# multiplex.net
KiCad netlist of a schematic drawn in EAGLE
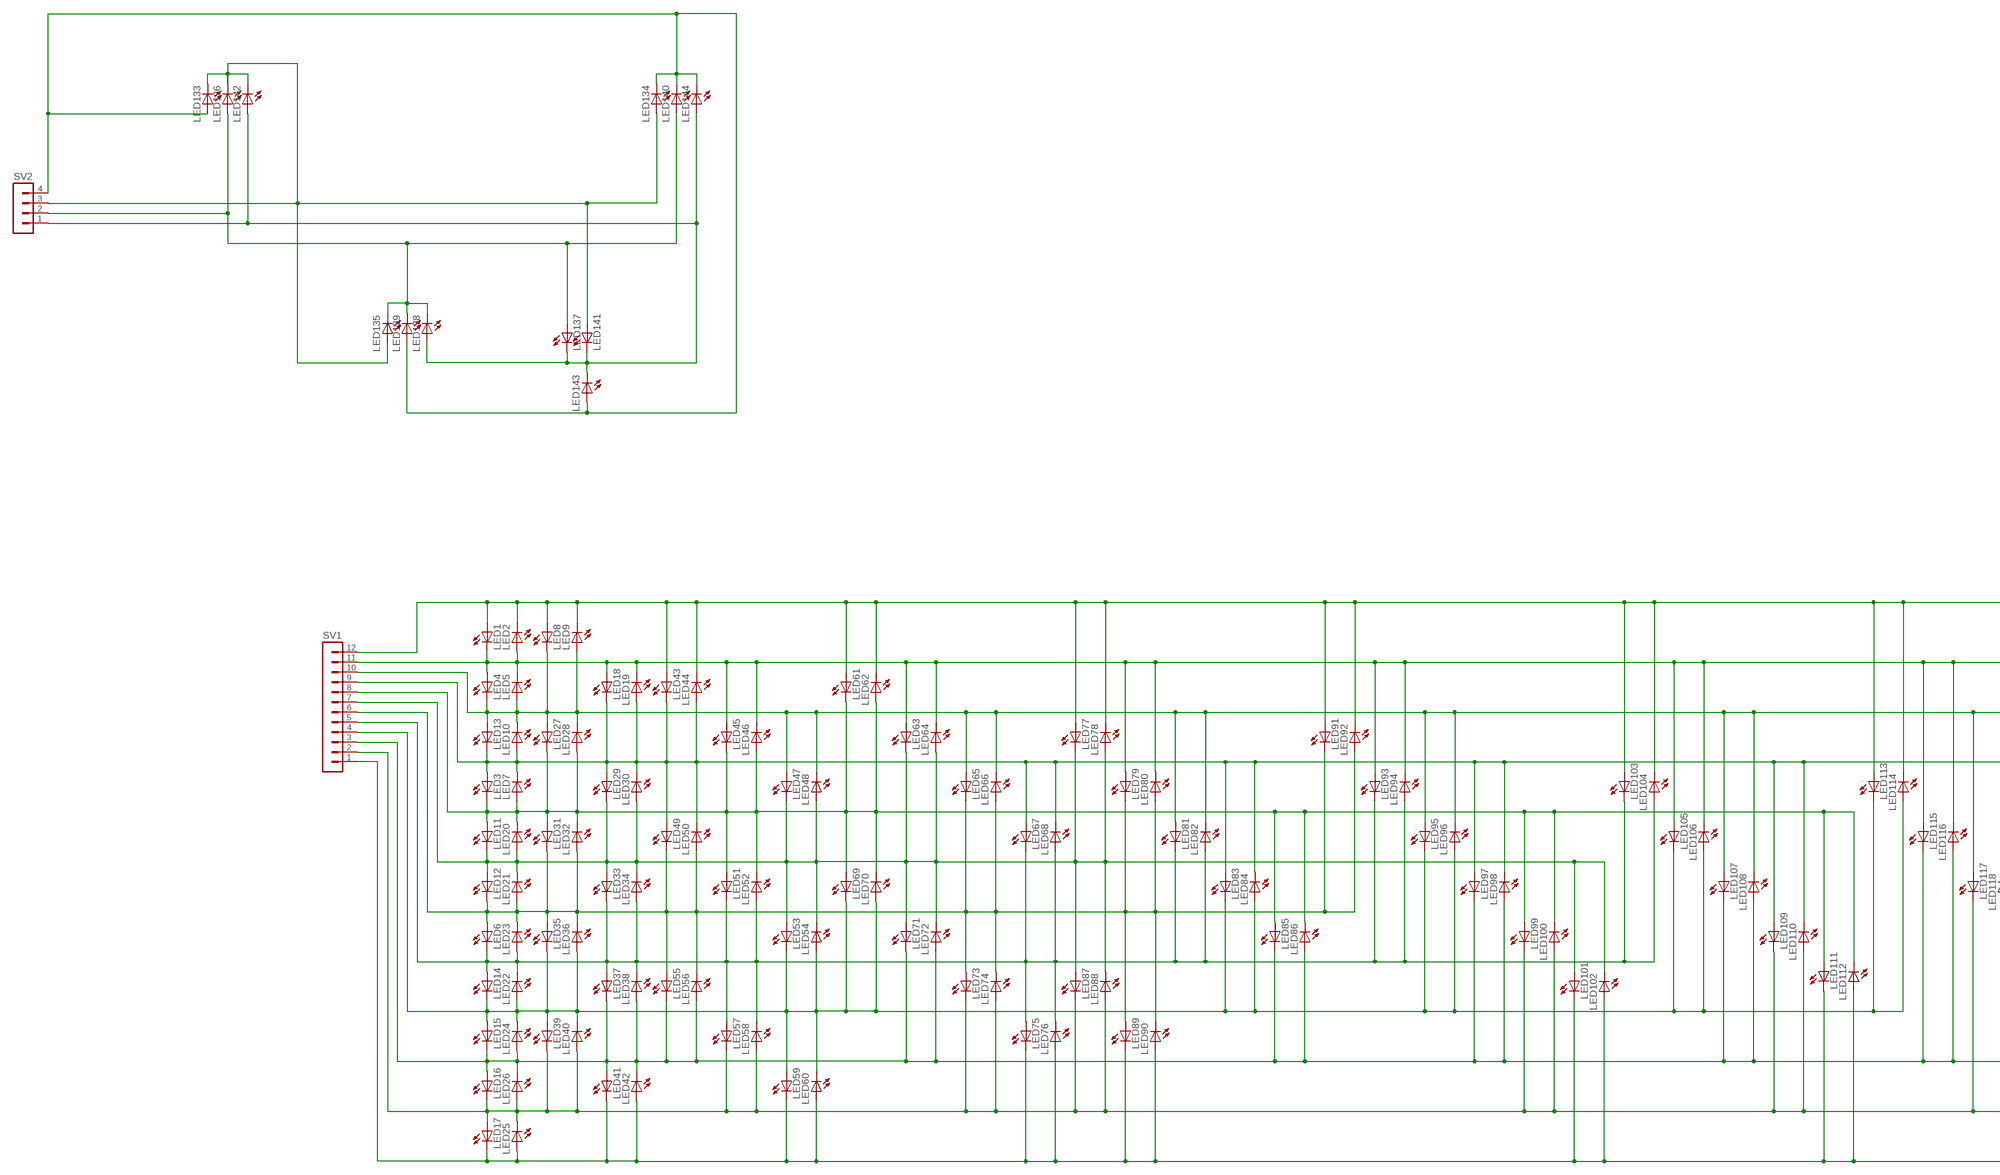
[diagram p0: schematic, sheet 1, part 1 of 2]
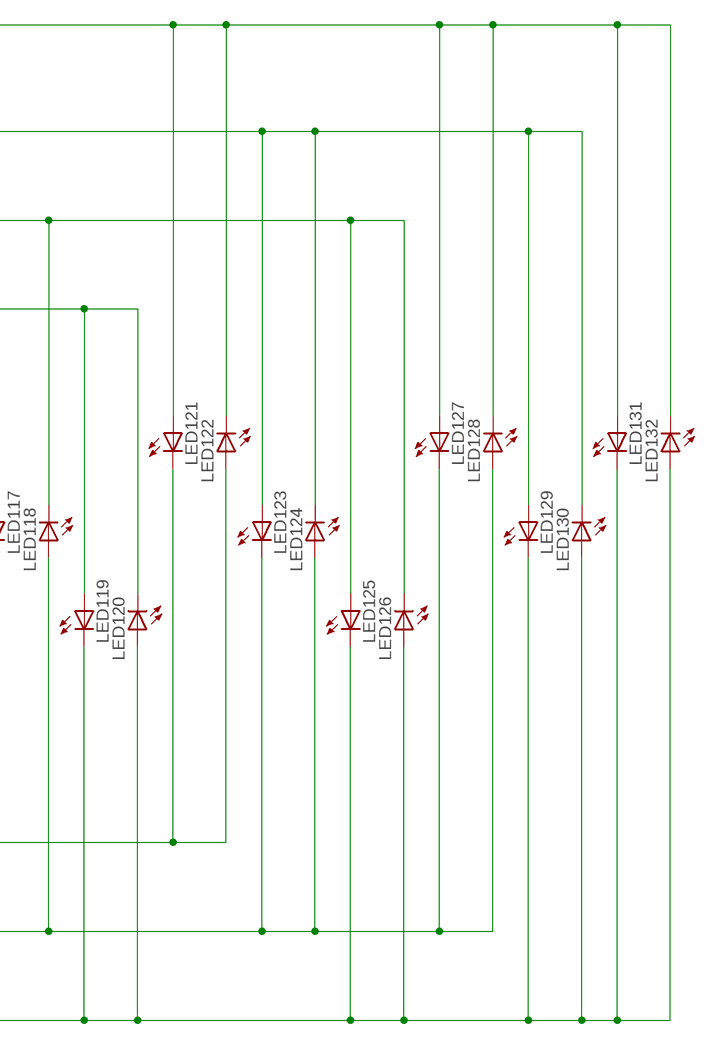
[diagram p1: schematic, sheet 1, part 2 of 2]

(export (version "E")
  (design (tool "Eeschema 10.0.6"))
  (components
    (comp (ref "LED1")
      (value "LED5MM")
      (footprint "eagle-import:LED5MM")
      (libsource (lib "eagle-import") (part "LED5MM"))
    )
    (comp (ref "LED2")
      (value "LED5MM")
      (footprint "eagle-import:LED5MM")
      (libsource (lib "eagle-import") (part "LED5MM"))
    )
    (comp (ref "LED3")
      (value "LED5MM")
      (footprint "eagle-import:LED5MM")
      (libsource (lib "eagle-import") (part "LED5MM"))
    )
    (comp (ref "LED4")
      (value "LED5MM")
      (footprint "eagle-import:LED5MM")
      (libsource (lib "eagle-import") (part "LED5MM"))
    )
    (comp (ref "LED5")
      (value "LED5MM")
      (footprint "eagle-import:LED5MM")
      (libsource (lib "eagle-import") (part "LED5MM"))
    )
    (comp (ref "LED6")
      (value "LED5MM")
      (footprint "eagle-import:LED5MM")
      (libsource (lib "eagle-import") (part "LED5MM"))
    )
    (comp (ref "LED7")
      (value "LED5MM")
      (footprint "eagle-import:LED5MM")
      (libsource (lib "eagle-import") (part "LED5MM"))
    )
    (comp (ref "LED8")
      (value "LED5MM")
      (footprint "eagle-import:LED5MM")
      (libsource (lib "eagle-import") (part "LED5MM"))
    )
    (comp (ref "LED9")
      (value "LED5MM")
      (footprint "eagle-import:LED5MM")
      (libsource (lib "eagle-import") (part "LED5MM"))
    )
    (comp (ref "LED10")
      (value "LED5MM")
      (footprint "eagle-import:LED5MM")
      (libsource (lib "eagle-import") (part "LED5MM"))
    )
    (comp (ref "LED11")
      (value "LED5MM")
      (footprint "eagle-import:LED5MM")
      (libsource (lib "eagle-import") (part "LED5MM"))
    )
    (comp (ref "LED12")
      (value "LED5MM")
      (footprint "eagle-import:LED5MM")
      (libsource (lib "eagle-import") (part "LED5MM"))
    )
    (comp (ref "LED13")
      (value "LED5MM")
      (footprint "eagle-import:LED5MM")
      (libsource (lib "eagle-import") (part "LED5MM"))
    )
    (comp (ref "LED14")
      (value "LED5MM")
      (footprint "eagle-import:LED5MM")
      (libsource (lib "eagle-import") (part "LED5MM"))
    )
    (comp (ref "LED15")
      (value "LED5MM")
      (footprint "eagle-import:LED5MM")
      (libsource (lib "eagle-import") (part "LED5MM"))
    )
    (comp (ref "LED16")
      (value "LED5MM")
      (footprint "eagle-import:LED5MM")
      (libsource (lib "eagle-import") (part "LED5MM"))
    )
    (comp (ref "LED17")
      (value "LED5MM")
      (footprint "eagle-import:LED5MM")
      (libsource (lib "eagle-import") (part "LED5MM"))
    )
    (comp (ref "LED18")
      (value "LED5MM")
      (footprint "eagle-import:LED5MM")
      (libsource (lib "eagle-import") (part "LED5MM"))
    )
    (comp (ref "LED19")
      (value "LED5MM")
      (footprint "eagle-import:LED5MM")
      (libsource (lib "eagle-import") (part "LED5MM"))
    )
    (comp (ref "LED20")
      (value "LED5MM")
      (footprint "eagle-import:LED5MM")
      (libsource (lib "eagle-import") (part "LED5MM"))
    )
    (comp (ref "LED21")
      (value "LED5MM")
      (footprint "eagle-import:LED5MM")
      (libsource (lib "eagle-import") (part "LED5MM"))
    )
    (comp (ref "LED22")
      (value "LED5MM")
      (footprint "eagle-import:LED5MM")
      (libsource (lib "eagle-import") (part "LED5MM"))
    )
    (comp (ref "LED23")
      (value "LED5MM")
      (footprint "eagle-import:LED5MM")
      (libsource (lib "eagle-import") (part "LED5MM"))
    )
    (comp (ref "LED24")
      (value "LED5MM")
      (footprint "eagle-import:LED5MM")
      (libsource (lib "eagle-import") (part "LED5MM"))
    )
    (comp (ref "LED25")
      (value "LED5MM")
      (footprint "eagle-import:LED5MM")
      (libsource (lib "eagle-import") (part "LED5MM"))
    )
    (comp (ref "LED26")
      (value "LED5MM")
      (footprint "eagle-import:LED5MM")
      (libsource (lib "eagle-import") (part "LED5MM"))
    )
    (comp (ref "LED27")
      (value "LED5MM")
      (footprint "eagle-import:LED5MM")
      (libsource (lib "eagle-import") (part "LED5MM"))
    )
    (comp (ref "LED28")
      (value "LED5MM")
      (footprint "eagle-import:LED5MM")
      (libsource (lib "eagle-import") (part "LED5MM"))
    )
    (comp (ref "LED29")
      (value "LED5MM")
      (footprint "eagle-import:LED5MM")
      (libsource (lib "eagle-import") (part "LED5MM"))
    )
    (comp (ref "LED30")
      (value "LED5MM")
      (footprint "eagle-import:LED5MM")
      (libsource (lib "eagle-import") (part "LED5MM"))
    )
    (comp (ref "LED31")
      (value "LED5MM")
      (footprint "eagle-import:LED5MM")
      (libsource (lib "eagle-import") (part "LED5MM"))
    )
    (comp (ref "LED32")
      (value "LED5MM")
      (footprint "eagle-import:LED5MM")
      (libsource (lib "eagle-import") (part "LED5MM"))
    )
    (comp (ref "LED33")
      (value "LED5MM")
      (footprint "eagle-import:LED5MM")
      (libsource (lib "eagle-import") (part "LED5MM"))
    )
    (comp (ref "LED34")
      (value "LED5MM")
      (footprint "eagle-import:LED5MM")
      (libsource (lib "eagle-import") (part "LED5MM"))
    )
    (comp (ref "LED35")
      (value "LED5MM")
      (footprint "eagle-import:LED5MM")
      (libsource (lib "eagle-import") (part "LED5MM"))
    )
    (comp (ref "LED36")
      (value "LED5MM")
      (footprint "eagle-import:LED5MM")
      (libsource (lib "eagle-import") (part "LED5MM"))
    )
    (comp (ref "LED37")
      (value "LED5MM")
      (footprint "eagle-import:LED5MM")
      (libsource (lib "eagle-import") (part "LED5MM"))
    )
    (comp (ref "LED38")
      (value "LED5MM")
      (footprint "eagle-import:LED5MM")
      (libsource (lib "eagle-import") (part "LED5MM"))
    )
    (comp (ref "LED39")
      (value "LED5MM")
      (footprint "eagle-import:LED5MM")
      (libsource (lib "eagle-import") (part "LED5MM"))
    )
    (comp (ref "LED40")
      (value "LED5MM")
      (footprint "eagle-import:LED5MM")
      (libsource (lib "eagle-import") (part "LED5MM"))
    )
    (comp (ref "LED41")
      (value "LED5MM")
      (footprint "eagle-import:LED5MM")
      (libsource (lib "eagle-import") (part "LED5MM"))
    )
    (comp (ref "LED42")
      (value "LED5MM")
      (footprint "eagle-import:LED5MM")
      (libsource (lib "eagle-import") (part "LED5MM"))
    )
    (comp (ref "LED43")
      (value "LED5MM")
      (footprint "eagle-import:LED5MM")
      (libsource (lib "eagle-import") (part "LED5MM"))
    )
    (comp (ref "LED44")
      (value "LED5MM")
      (footprint "eagle-import:LED5MM")
      (libsource (lib "eagle-import") (part "LED5MM"))
    )
    (comp (ref "LED45")
      (value "LED5MM")
      (footprint "eagle-import:LED5MM")
      (libsource (lib "eagle-import") (part "LED5MM"))
    )
    (comp (ref "LED46")
      (value "LED5MM")
      (footprint "eagle-import:LED5MM")
      (libsource (lib "eagle-import") (part "LED5MM"))
    )
    (comp (ref "LED47")
      (value "LED5MM")
      (footprint "eagle-import:LED5MM")
      (libsource (lib "eagle-import") (part "LED5MM"))
    )
    (comp (ref "LED48")
      (value "LED5MM")
      (footprint "eagle-import:LED5MM")
      (libsource (lib "eagle-import") (part "LED5MM"))
    )
    (comp (ref "LED49")
      (value "LED5MM")
      (footprint "eagle-import:LED5MM")
      (libsource (lib "eagle-import") (part "LED5MM"))
    )
    (comp (ref "LED50")
      (value "LED5MM")
      (footprint "eagle-import:LED5MM")
      (libsource (lib "eagle-import") (part "LED5MM"))
    )
    (comp (ref "LED51")
      (value "LED5MM")
      (footprint "eagle-import:LED5MM")
      (libsource (lib "eagle-import") (part "LED5MM"))
    )
    (comp (ref "LED52")
      (value "LED5MM")
      (footprint "eagle-import:LED5MM")
      (libsource (lib "eagle-import") (part "LED5MM"))
    )
    (comp (ref "LED53")
      (value "LED5MM")
      (footprint "eagle-import:LED5MM")
      (libsource (lib "eagle-import") (part "LED5MM"))
    )
    (comp (ref "LED54")
      (value "LED5MM")
      (footprint "eagle-import:LED5MM")
      (libsource (lib "eagle-import") (part "LED5MM"))
    )
    (comp (ref "LED55")
      (value "LED5MM")
      (footprint "eagle-import:LED5MM")
      (libsource (lib "eagle-import") (part "LED5MM"))
    )
    (comp (ref "LED56")
      (value "LED5MM")
      (footprint "eagle-import:LED5MM")
      (libsource (lib "eagle-import") (part "LED5MM"))
    )
    (comp (ref "LED57")
      (value "LED5MM")
      (footprint "eagle-import:LED5MM")
      (libsource (lib "eagle-import") (part "LED5MM"))
    )
    (comp (ref "LED58")
      (value "LED5MM")
      (footprint "eagle-import:LED5MM")
      (libsource (lib "eagle-import") (part "LED5MM"))
    )
    (comp (ref "LED59")
      (value "LED5MM")
      (footprint "eagle-import:LED5MM")
      (libsource (lib "eagle-import") (part "LED5MM"))
    )
    (comp (ref "LED60")
      (value "LED5MM")
      (footprint "eagle-import:LED5MM")
      (libsource (lib "eagle-import") (part "LED5MM"))
    )
    (comp (ref "LED61")
      (value "LED5MM")
      (footprint "eagle-import:LED5MM")
      (libsource (lib "eagle-import") (part "LED5MM"))
    )
    (comp (ref "LED62")
      (value "LED5MM")
      (footprint "eagle-import:LED5MM")
      (libsource (lib "eagle-import") (part "LED5MM"))
    )
    (comp (ref "LED63")
      (value "LED5MM")
      (footprint "eagle-import:LED5MM")
      (libsource (lib "eagle-import") (part "LED5MM"))
    )
    (comp (ref "LED64")
      (value "LED5MM")
      (footprint "eagle-import:LED5MM")
      (libsource (lib "eagle-import") (part "LED5MM"))
    )
    (comp (ref "LED65")
      (value "LED5MM")
      (footprint "eagle-import:LED5MM")
      (libsource (lib "eagle-import") (part "LED5MM"))
    )
    (comp (ref "LED66")
      (value "LED5MM")
      (footprint "eagle-import:LED5MM")
      (libsource (lib "eagle-import") (part "LED5MM"))
    )
    (comp (ref "LED67")
      (value "LED5MM")
      (footprint "eagle-import:LED5MM")
      (libsource (lib "eagle-import") (part "LED5MM"))
    )
    (comp (ref "LED68")
      (value "LED5MM")
      (footprint "eagle-import:LED5MM")
      (libsource (lib "eagle-import") (part "LED5MM"))
    )
    (comp (ref "LED69")
      (value "LED5MM")
      (footprint "eagle-import:LED5MM")
      (libsource (lib "eagle-import") (part "LED5MM"))
    )
    (comp (ref "LED70")
      (value "LED5MM")
      (footprint "eagle-import:LED5MM")
      (libsource (lib "eagle-import") (part "LED5MM"))
    )
    (comp (ref "LED71")
      (value "LED5MM")
      (footprint "eagle-import:LED5MM")
      (libsource (lib "eagle-import") (part "LED5MM"))
    )
    (comp (ref "LED72")
      (value "LED5MM")
      (footprint "eagle-import:LED5MM")
      (libsource (lib "eagle-import") (part "LED5MM"))
    )
    (comp (ref "LED73")
      (value "LED5MM")
      (footprint "eagle-import:LED5MM")
      (libsource (lib "eagle-import") (part "LED5MM"))
    )
    (comp (ref "LED74")
      (value "LED5MM")
      (footprint "eagle-import:LED5MM")
      (libsource (lib "eagle-import") (part "LED5MM"))
    )
    (comp (ref "LED75")
      (value "LED5MM")
      (footprint "eagle-import:LED5MM")
      (libsource (lib "eagle-import") (part "LED5MM"))
    )
    (comp (ref "LED76")
      (value "LED5MM")
      (footprint "eagle-import:LED5MM")
      (libsource (lib "eagle-import") (part "LED5MM"))
    )
    (comp (ref "LED77")
      (value "LED5MM")
      (footprint "eagle-import:LED5MM")
      (libsource (lib "eagle-import") (part "LED5MM"))
    )
    (comp (ref "LED78")
      (value "LED5MM")
      (footprint "eagle-import:LED5MM")
      (libsource (lib "eagle-import") (part "LED5MM"))
    )
    (comp (ref "LED79")
      (value "LED5MM")
      (footprint "eagle-import:LED5MM")
      (libsource (lib "eagle-import") (part "LED5MM"))
    )
    (comp (ref "LED80")
      (value "LED5MM")
      (footprint "eagle-import:LED5MM")
      (libsource (lib "eagle-import") (part "LED5MM"))
    )
    (comp (ref "LED81")
      (value "LED5MM")
      (footprint "eagle-import:LED5MM")
      (libsource (lib "eagle-import") (part "LED5MM"))
    )
    (comp (ref "LED82")
      (value "LED5MM")
      (footprint "eagle-import:LED5MM")
      (libsource (lib "eagle-import") (part "LED5MM"))
    )
    (comp (ref "LED83")
      (value "LED5MM")
      (footprint "eagle-import:LED5MM")
      (libsource (lib "eagle-import") (part "LED5MM"))
    )
    (comp (ref "LED84")
      (value "LED5MM")
      (footprint "eagle-import:LED5MM")
      (libsource (lib "eagle-import") (part "LED5MM"))
    )
    (comp (ref "LED85")
      (value "LED5MM")
      (footprint "eagle-import:LED5MM")
      (libsource (lib "eagle-import") (part "LED5MM"))
    )
    (comp (ref "LED86")
      (value "LED5MM")
      (footprint "eagle-import:LED5MM")
      (libsource (lib "eagle-import") (part "LED5MM"))
    )
    (comp (ref "LED87")
      (value "LED5MM")
      (footprint "eagle-import:LED5MM")
      (libsource (lib "eagle-import") (part "LED5MM"))
    )
    (comp (ref "LED88")
      (value "LED5MM")
      (footprint "eagle-import:LED5MM")
      (libsource (lib "eagle-import") (part "LED5MM"))
    )
    (comp (ref "LED89")
      (value "LED5MM")
      (footprint "eagle-import:LED5MM")
      (libsource (lib "eagle-import") (part "LED5MM"))
    )
    (comp (ref "LED90")
      (value "LED5MM")
      (footprint "eagle-import:LED5MM")
      (libsource (lib "eagle-import") (part "LED5MM"))
    )
    (comp (ref "LED91")
      (value "LED5MM")
      (footprint "eagle-import:LED5MM")
      (libsource (lib "eagle-import") (part "LED5MM"))
    )
    (comp (ref "LED92")
      (value "LED5MM")
      (footprint "eagle-import:LED5MM")
      (libsource (lib "eagle-import") (part "LED5MM"))
    )
    (comp (ref "LED93")
      (value "LED5MM")
      (footprint "eagle-import:LED5MM")
      (libsource (lib "eagle-import") (part "LED5MM"))
    )
    (comp (ref "LED94")
      (value "LED5MM")
      (footprint "eagle-import:LED5MM")
      (libsource (lib "eagle-import") (part "LED5MM"))
    )
    (comp (ref "LED95")
      (value "LED5MM")
      (footprint "eagle-import:LED5MM")
      (libsource (lib "eagle-import") (part "LED5MM"))
    )
    (comp (ref "LED96")
      (value "LED5MM")
      (footprint "eagle-import:LED5MM")
      (libsource (lib "eagle-import") (part "LED5MM"))
    )
    (comp (ref "LED97")
      (value "LED5MM")
      (footprint "eagle-import:LED5MM")
      (libsource (lib "eagle-import") (part "LED5MM"))
    )
    (comp (ref "LED98")
      (value "LED5MM")
      (footprint "eagle-import:LED5MM")
      (libsource (lib "eagle-import") (part "LED5MM"))
    )
    (comp (ref "LED99")
      (value "LED5MM")
      (footprint "eagle-import:LED5MM")
      (libsource (lib "eagle-import") (part "LED5MM"))
    )
    (comp (ref "LED100")
      (value "LED5MM")
      (footprint "eagle-import:LED5MM")
      (libsource (lib "eagle-import") (part "LED5MM"))
    )
    (comp (ref "LED101")
      (value "LED5MM")
      (footprint "eagle-import:LED5MM")
      (libsource (lib "eagle-import") (part "LED5MM"))
    )
    (comp (ref "LED102")
      (value "LED5MM")
      (footprint "eagle-import:LED5MM")
      (libsource (lib "eagle-import") (part "LED5MM"))
    )
    (comp (ref "LED103")
      (value "LED5MM")
      (footprint "eagle-import:LED5MM")
      (libsource (lib "eagle-import") (part "LED5MM"))
    )
    (comp (ref "LED104")
      (value "LED5MM")
      (footprint "eagle-import:LED5MM")
      (libsource (lib "eagle-import") (part "LED5MM"))
    )
    (comp (ref "LED105")
      (value "LED5MM")
      (footprint "eagle-import:LED5MM")
      (libsource (lib "eagle-import") (part "LED5MM"))
    )
    (comp (ref "LED106")
      (value "LED5MM")
      (footprint "eagle-import:LED5MM")
      (libsource (lib "eagle-import") (part "LED5MM"))
    )
    (comp (ref "LED107")
      (value "LED5MM")
      (footprint "eagle-import:LED5MM")
      (libsource (lib "eagle-import") (part "LED5MM"))
    )
    (comp (ref "LED108")
      (value "LED5MM")
      (footprint "eagle-import:LED5MM")
      (libsource (lib "eagle-import") (part "LED5MM"))
    )
    (comp (ref "LED109")
      (value "LED5MM")
      (footprint "eagle-import:LED5MM")
      (libsource (lib "eagle-import") (part "LED5MM"))
    )
    (comp (ref "LED110")
      (value "LED5MM")
      (footprint "eagle-import:LED5MM")
      (libsource (lib "eagle-import") (part "LED5MM"))
    )
    (comp (ref "LED111")
      (value "LED5MM")
      (footprint "eagle-import:LED5MM")
      (libsource (lib "eagle-import") (part "LED5MM"))
    )
    (comp (ref "LED112")
      (value "LED5MM")
      (footprint "eagle-import:LED5MM")
      (libsource (lib "eagle-import") (part "LED5MM"))
    )
    (comp (ref "LED113")
      (value "LED5MM")
      (footprint "eagle-import:LED5MM")
      (libsource (lib "eagle-import") (part "LED5MM"))
    )
    (comp (ref "LED114")
      (value "LED5MM")
      (footprint "eagle-import:LED5MM")
      (libsource (lib "eagle-import") (part "LED5MM"))
    )
    (comp (ref "LED115")
      (value "LED5MM")
      (footprint "eagle-import:LED5MM")
      (libsource (lib "eagle-import") (part "LED5MM"))
    )
    (comp (ref "LED116")
      (value "LED5MM")
      (footprint "eagle-import:LED5MM")
      (libsource (lib "eagle-import") (part "LED5MM"))
    )
    (comp (ref "LED117")
      (value "LED5MM")
      (footprint "eagle-import:LED5MM")
      (libsource (lib "eagle-import") (part "LED5MM"))
    )
    (comp (ref "LED118")
      (value "LED5MM")
      (footprint "eagle-import:LED5MM")
      (libsource (lib "eagle-import") (part "LED5MM"))
    )
    (comp (ref "LED119")
      (value "LED5MM")
      (footprint "eagle-import:LED5MM")
      (libsource (lib "eagle-import") (part "LED5MM"))
    )
    (comp (ref "LED120")
      (value "LED5MM")
      (footprint "eagle-import:LED5MM")
      (libsource (lib "eagle-import") (part "LED5MM"))
    )
    (comp (ref "LED121")
      (value "LED5MM")
      (footprint "eagle-import:LED5MM")
      (libsource (lib "eagle-import") (part "LED5MM"))
    )
    (comp (ref "LED122")
      (value "LED5MM")
      (footprint "eagle-import:LED5MM")
      (libsource (lib "eagle-import") (part "LED5MM"))
    )
    (comp (ref "LED123")
      (value "LED5MM")
      (footprint "eagle-import:LED5MM")
      (libsource (lib "eagle-import") (part "LED5MM"))
    )
    (comp (ref "LED124")
      (value "LED5MM")
      (footprint "eagle-import:LED5MM")
      (libsource (lib "eagle-import") (part "LED5MM"))
    )
    (comp (ref "LED125")
      (value "LED5MM")
      (footprint "eagle-import:LED5MM")
      (libsource (lib "eagle-import") (part "LED5MM"))
    )
    (comp (ref "LED126")
      (value "LED5MM")
      (footprint "eagle-import:LED5MM")
      (libsource (lib "eagle-import") (part "LED5MM"))
    )
    (comp (ref "LED127")
      (value "LED5MM")
      (footprint "eagle-import:LED5MM")
      (libsource (lib "eagle-import") (part "LED5MM"))
    )
    (comp (ref "LED128")
      (value "LED5MM")
      (footprint "eagle-import:LED5MM")
      (libsource (lib "eagle-import") (part "LED5MM"))
    )
    (comp (ref "LED129")
      (value "LED5MM")
      (footprint "eagle-import:LED5MM")
      (libsource (lib "eagle-import") (part "LED5MM"))
    )
    (comp (ref "LED130")
      (value "LED5MM")
      (footprint "eagle-import:LED5MM")
      (libsource (lib "eagle-import") (part "LED5MM"))
    )
    (comp (ref "LED131")
      (value "LED5MM")
      (footprint "eagle-import:LED5MM")
      (libsource (lib "eagle-import") (part "LED5MM"))
    )
    (comp (ref "LED132")
      (value "LED5MM")
      (footprint "eagle-import:LED5MM")
      (libsource (lib "eagle-import") (part "LED5MM"))
    )
    (comp (ref "LED133")
      (value "LED5MM")
      (footprint "eagle-import:LED5MM")
      (libsource (lib "eagle-import") (part "LED5MM"))
    )
    (comp (ref "LED134")
      (value "LED5MM")
      (footprint "eagle-import:LED5MM")
      (libsource (lib "eagle-import") (part "LED5MM"))
    )
    (comp (ref "LED135")
      (value "LED5MM")
      (footprint "eagle-import:LED5MM")
      (libsource (lib "eagle-import") (part "LED5MM"))
    )
    (comp (ref "LED136")
      (value "LED5MM")
      (footprint "eagle-import:LED5MM")
      (libsource (lib "eagle-import") (part "LED5MM"))
    )
    (comp (ref "LED137")
      (value "LED5MM")
      (footprint "eagle-import:LED5MM")
      (libsource (lib "eagle-import") (part "LED5MM"))
    )
    (comp (ref "LED138")
      (value "LED5MM")
      (footprint "eagle-import:LED5MM")
      (libsource (lib "eagle-import") (part "LED5MM"))
    )
    (comp (ref "LED139")
      (value "LED5MM")
      (footprint "eagle-import:LED5MM")
      (libsource (lib "eagle-import") (part "LED5MM"))
    )
    (comp (ref "LED140")
      (value "LED5MM")
      (footprint "eagle-import:LED5MM")
      (libsource (lib "eagle-import") (part "LED5MM"))
    )
    (comp (ref "LED141")
      (value "LED5MM")
      (footprint "eagle-import:LED5MM")
      (libsource (lib "eagle-import") (part "LED5MM"))
    )
    (comp (ref "LED142")
      (value "LED5MM")
      (footprint "eagle-import:LED5MM")
      (libsource (lib "eagle-import") (part "LED5MM"))
    )
    (comp (ref "LED143")
      (value "LED5MM")
      (footprint "eagle-import:LED5MM")
      (libsource (lib "eagle-import") (part "LED5MM"))
    )
    (comp (ref "LED144")
      (value "LED5MM")
      (footprint "eagle-import:LED5MM")
      (libsource (lib "eagle-import") (part "LED5MM"))
    )
    (comp (ref "SV1")
      (value "MA12-1")
      (footprint "eagle-import:MA12-1")
      (libsource (lib "eagle-import") (part "MA12-1"))
    )
    (comp (ref "SV2")
      (value "MA04-1")
      (footprint "eagle-import:MA04-1")
      (libsource (lib "eagle-import") (part "MA04-1"))
    )
  )
  (nets
    (net (code "1") (name "Net-(LED1-C)") (class "Default")
      (node (ref "LED1") (pin "K") (pinfunction "C_K") (pintype "passive"))
      (node (ref "LED105") (pin "A") (pinfunction "A_A") (pintype "passive"))
      (node (ref "LED106") (pin "K") (pinfunction "C_K") (pintype "passive"))
      (node (ref "LED115") (pin "A") (pinfunction "A_A") (pintype "passive"))
      (node (ref "LED116") (pin "K") (pinfunction "C_K") (pintype "passive"))
      (node (ref "LED123") (pin "A") (pinfunction "A_A") (pintype "passive"))
      (node (ref "LED124") (pin "K") (pinfunction "C_K") (pintype "passive"))
      (node (ref "LED129") (pin "A") (pinfunction "A_A") (pintype "passive"))
      (node (ref "LED130") (pin "K") (pinfunction "C_K") (pintype "passive"))
      (node (ref "LED18") (pin "A") (pinfunction "A_A") (pintype "passive"))
      (node (ref "LED19") (pin "K") (pinfunction "C_K") (pintype "passive"))
      (node (ref "LED2") (pin "A") (pinfunction "A_A") (pintype "passive"))
      (node (ref "LED4") (pin "A") (pinfunction "A_A") (pintype "passive"))
      (node (ref "LED45") (pin "A") (pinfunction "A_A") (pintype "passive"))
      (node (ref "LED46") (pin "K") (pinfunction "C_K") (pintype "passive"))
      (node (ref "LED5") (pin "K") (pinfunction "C_K") (pintype "passive"))
      (node (ref "LED63") (pin "A") (pinfunction "A_A") (pintype "passive"))
      (node (ref "LED64") (pin "K") (pinfunction "C_K") (pintype "passive"))
      (node (ref "LED79") (pin "A") (pinfunction "A_A") (pintype "passive"))
      (node (ref "LED80") (pin "K") (pinfunction "C_K") (pintype "passive"))
      (node (ref "LED93") (pin "A") (pinfunction "A_A") (pintype "passive"))
      (node (ref "LED94") (pin "K") (pinfunction "C_K") (pintype "passive"))
      (node (ref "SV1") (pin "11") (pinfunction "11_11") (pintype "passive"))
    )
    (net (code "2") (name "Net-(LED10-C)") (class "Default")
      (node (ref "LED10") (pin "K") (pinfunction "C_K") (pintype "passive"))
      (node (ref "LED107") (pin "A") (pinfunction "A_A") (pintype "passive"))
      (node (ref "LED108") (pin "K") (pinfunction "C_K") (pintype "passive"))
      (node (ref "LED117") (pin "A") (pinfunction "A_A") (pintype "passive"))
      (node (ref "LED118") (pin "K") (pinfunction "C_K") (pintype "passive"))
      (node (ref "LED125") (pin "A") (pinfunction "A_A") (pintype "passive"))
      (node (ref "LED126") (pin "K") (pinfunction "C_K") (pintype "passive"))
      (node (ref "LED13") (pin "A") (pinfunction "A_A") (pintype "passive"))
      (node (ref "LED27") (pin "A") (pinfunction "A_A") (pintype "passive"))
      (node (ref "LED28") (pin "K") (pinfunction "C_K") (pintype "passive"))
      (node (ref "LED4") (pin "K") (pinfunction "C_K") (pintype "passive"))
      (node (ref "LED47") (pin "A") (pinfunction "A_A") (pintype "passive"))
      (node (ref "LED48") (pin "K") (pinfunction "C_K") (pintype "passive"))
      (node (ref "LED5") (pin "A") (pinfunction "A_A") (pintype "passive"))
      (node (ref "LED65") (pin "A") (pinfunction "A_A") (pintype "passive"))
      (node (ref "LED66") (pin "K") (pinfunction "C_K") (pintype "passive"))
      (node (ref "LED8") (pin "K") (pinfunction "C_K") (pintype "passive"))
      (node (ref "LED81") (pin "A") (pinfunction "A_A") (pintype "passive"))
      (node (ref "LED82") (pin "K") (pinfunction "C_K") (pintype "passive"))
      (node (ref "LED9") (pin "A") (pinfunction "A_A") (pintype "passive"))
      (node (ref "LED95") (pin "A") (pinfunction "A_A") (pintype "passive"))
      (node (ref "LED96") (pin "K") (pinfunction "C_K") (pintype "passive"))
      (node (ref "SV1") (pin "10") (pinfunction "10_10") (pintype "passive"))
    )
    (net (code "3") (name "Net-(LED12-C)") (class "Default")
      (node (ref "LED12") (pin "K") (pinfunction "C_K") (pintype "passive"))
      (node (ref "LED21") (pin "A") (pinfunction "A_A") (pintype "passive"))
      (node (ref "LED23") (pin "K") (pinfunction "C_K") (pintype "passive"))
      (node (ref "LED31") (pin "K") (pinfunction "C_K") (pintype "passive"))
      (node (ref "LED32") (pin "A") (pinfunction "A_A") (pintype "passive"))
      (node (ref "LED35") (pin "A") (pinfunction "A_A") (pintype "passive"))
      (node (ref "LED36") (pin "K") (pinfunction "C_K") (pintype "passive"))
      (node (ref "LED49") (pin "K") (pinfunction "C_K") (pintype "passive"))
      (node (ref "LED50") (pin "A") (pinfunction "A_A") (pintype "passive"))
      (node (ref "LED55") (pin "A") (pinfunction "A_A") (pintype "passive"))
      (node (ref "LED56") (pin "K") (pinfunction "C_K") (pintype "passive"))
      (node (ref "LED6") (pin "A") (pinfunction "A_A") (pintype "passive"))
      (node (ref "LED65") (pin "K") (pinfunction "C_K") (pintype "passive"))
      (node (ref "LED66") (pin "A") (pinfunction "A_A") (pintype "passive"))
      (node (ref "LED73") (pin "A") (pinfunction "A_A") (pintype "passive"))
      (node (ref "LED74") (pin "K") (pinfunction "C_K") (pintype "passive"))
      (node (ref "LED79") (pin "K") (pinfunction "C_K") (pintype "passive"))
      (node (ref "LED80") (pin "A") (pinfunction "A_A") (pintype "passive"))
      (node (ref "LED89") (pin "A") (pinfunction "A_A") (pintype "passive"))
      (node (ref "LED90") (pin "K") (pinfunction "C_K") (pintype "passive"))
      (node (ref "LED91") (pin "K") (pinfunction "C_K") (pintype "passive"))
      (node (ref "LED92") (pin "A") (pinfunction "A_A") (pintype "passive"))
      (node (ref "SV1") (pin "6") (pinfunction "6_6") (pintype "passive"))
    )
    (net (code "4") (name "Net-(LED100-C)") (class "Default")
      (node (ref "LED100") (pin "K") (pinfunction "C_K") (pintype "passive"))
      (node (ref "LED11") (pin "A") (pinfunction "A_A") (pintype "passive"))
      (node (ref "LED111") (pin "A") (pinfunction "A_A") (pintype "passive"))
      (node (ref "LED112") (pin "K") (pinfunction "C_K") (pintype "passive"))
      (node (ref "LED20") (pin "K") (pinfunction "C_K") (pintype "passive"))
      (node (ref "LED27") (pin "K") (pinfunction "C_K") (pintype "passive"))
      (node (ref "LED28") (pin "A") (pinfunction "A_A") (pintype "passive"))
      (node (ref "LED3") (pin "K") (pinfunction "C_K") (pintype "passive"))
      (node (ref "LED31") (pin "A") (pinfunction "A_A") (pintype "passive"))
      (node (ref "LED32") (pin "K") (pinfunction "C_K") (pintype "passive"))
      (node (ref "LED45") (pin "K") (pinfunction "C_K") (pintype "passive"))
      (node (ref "LED46") (pin "A") (pinfunction "A_A") (pintype "passive"))
      (node (ref "LED51") (pin "A") (pinfunction "A_A") (pintype "passive"))
      (node (ref "LED52") (pin "K") (pinfunction "C_K") (pintype "passive"))
      (node (ref "LED61") (pin "K") (pinfunction "C_K") (pintype "passive"))
      (node (ref "LED62") (pin "A") (pinfunction "A_A") (pintype "passive"))
      (node (ref "LED69") (pin "A") (pinfunction "A_A") (pintype "passive"))
      (node (ref "LED7") (pin "A") (pinfunction "A_A") (pintype "passive"))
      (node (ref "LED70") (pin "K") (pinfunction "C_K") (pintype "passive"))
      (node (ref "LED85") (pin "A") (pinfunction "A_A") (pintype "passive"))
      (node (ref "LED86") (pin "K") (pinfunction "C_K") (pintype "passive"))
      (node (ref "LED99") (pin "A") (pinfunction "A_A") (pintype "passive"))
      (node (ref "SV1") (pin "8") (pinfunction "8_8") (pintype "passive"))
    )
    (net (code "5") (name "Net-(LED101-C)") (class "Default")
      (node (ref "LED101") (pin "K") (pinfunction "C_K") (pintype "passive"))
      (node (ref "LED102") (pin "A") (pinfunction "A_A") (pintype "passive"))
      (node (ref "LED111") (pin "K") (pinfunction "C_K") (pintype "passive"))
      (node (ref "LED112") (pin "A") (pinfunction "A_A") (pintype "passive"))
      (node (ref "LED119") (pin "K") (pinfunction "C_K") (pintype "passive"))
      (node (ref "LED120") (pin "A") (pinfunction "A_A") (pintype "passive"))
      (node (ref "LED125") (pin "K") (pinfunction "C_K") (pintype "passive"))
      (node (ref "LED126") (pin "A") (pinfunction "A_A") (pintype "passive"))
      (node (ref "LED129") (pin "K") (pinfunction "C_K") (pintype "passive"))
      (node (ref "LED130") (pin "A") (pinfunction "A_A") (pintype "passive"))
      (node (ref "LED131") (pin "K") (pinfunction "C_K") (pintype "passive"))
      (node (ref "LED132") (pin "A") (pinfunction "A_A") (pintype "passive"))
      (node (ref "LED17") (pin "K") (pinfunction "C_K") (pintype "passive"))
      (node (ref "LED25") (pin "A") (pinfunction "A_A") (pintype "passive"))
      (node (ref "LED41") (pin "K") (pinfunction "C_K") (pintype "passive"))
      (node (ref "LED42") (pin "A") (pinfunction "A_A") (pintype "passive"))
      (node (ref "LED59") (pin "K") (pinfunction "C_K") (pintype "passive"))
      (node (ref "LED60") (pin "A") (pinfunction "A_A") (pintype "passive"))
      (node (ref "LED75") (pin "K") (pinfunction "C_K") (pintype "passive"))
      (node (ref "LED76") (pin "A") (pinfunction "A_A") (pintype "passive"))
      (node (ref "LED89") (pin "K") (pinfunction "C_K") (pintype "passive"))
      (node (ref "LED90") (pin "A") (pinfunction "A_A") (pintype "passive"))
      (node (ref "SV1") (pin "1") (pinfunction "1_1") (pintype "passive"))
    )
    (net (code "6") (name "Net-(LED102-C)") (class "Default")
      (node (ref "LED101") (pin "A") (pinfunction "A_A") (pintype "passive"))
      (node (ref "LED102") (pin "K") (pinfunction "C_K") (pintype "passive"))
      (node (ref "LED11") (pin "K") (pinfunction "C_K") (pintype "passive"))
      (node (ref "LED12") (pin "A") (pinfunction "A_A") (pintype "passive"))
      (node (ref "LED20") (pin "A") (pinfunction "A_A") (pintype "passive"))
      (node (ref "LED21") (pin "K") (pinfunction "C_K") (pintype "passive"))
      (node (ref "LED29") (pin "K") (pinfunction "C_K") (pintype "passive"))
      (node (ref "LED30") (pin "A") (pinfunction "A_A") (pintype "passive"))
      (node (ref "LED33") (pin "A") (pinfunction "A_A") (pintype "passive"))
      (node (ref "LED34") (pin "K") (pinfunction "C_K") (pintype "passive"))
      (node (ref "LED47") (pin "K") (pinfunction "C_K") (pintype "passive"))
      (node (ref "LED48") (pin "A") (pinfunction "A_A") (pintype "passive"))
      (node (ref "LED53") (pin "A") (pinfunction "A_A") (pintype "passive"))
      (node (ref "LED54") (pin "K") (pinfunction "C_K") (pintype "passive"))
      (node (ref "LED63") (pin "K") (pinfunction "C_K") (pintype "passive"))
      (node (ref "LED64") (pin "A") (pinfunction "A_A") (pintype "passive"))
      (node (ref "LED71") (pin "A") (pinfunction "A_A") (pintype "passive"))
      (node (ref "LED72") (pin "K") (pinfunction "C_K") (pintype "passive"))
      (node (ref "LED77") (pin "K") (pinfunction "C_K") (pintype "passive"))
      (node (ref "LED78") (pin "A") (pinfunction "A_A") (pintype "passive"))
      (node (ref "LED87") (pin "A") (pinfunction "A_A") (pintype "passive"))
      (node (ref "LED88") (pin "K") (pinfunction "C_K") (pintype "passive"))
      (node (ref "SV1") (pin "7") (pinfunction "7_7") (pintype "passive"))
    )
    (net (code "7") (name "Net-(LED103-C)") (class "Default")
      (node (ref "LED103") (pin "K") (pinfunction "C_K") (pintype "passive"))
      (node (ref "LED104") (pin "A") (pinfunction "A_A") (pintype "passive"))
      (node (ref "LED14") (pin "A") (pinfunction "A_A") (pintype "passive"))
      (node (ref "LED22") (pin "K") (pinfunction "C_K") (pintype "passive"))
      (node (ref "LED23") (pin "A") (pinfunction "A_A") (pintype "passive"))
      (node (ref "LED33") (pin "K") (pinfunction "C_K") (pintype "passive"))
      (node (ref "LED34") (pin "A") (pinfunction "A_A") (pintype "passive"))
      (node (ref "LED37") (pin "A") (pinfunction "A_A") (pintype "passive"))
      (node (ref "LED38") (pin "K") (pinfunction "C_K") (pintype "passive"))
      (node (ref "LED51") (pin "K") (pinfunction "C_K") (pintype "passive"))
      (node (ref "LED52") (pin "A") (pinfunction "A_A") (pintype "passive"))
      (node (ref "LED57") (pin "A") (pinfunction "A_A") (pintype "passive"))
      (node (ref "LED58") (pin "K") (pinfunction "C_K") (pintype "passive"))
      (node (ref "LED6") (pin "K") (pinfunction "C_K") (pintype "passive"))
      (node (ref "LED67") (pin "K") (pinfunction "C_K") (pintype "passive"))
      (node (ref "LED68") (pin "A") (pinfunction "A_A") (pintype "passive"))
      (node (ref "LED75") (pin "A") (pinfunction "A_A") (pintype "passive"))
      (node (ref "LED76") (pin "K") (pinfunction "C_K") (pintype "passive"))
      (node (ref "LED81") (pin "K") (pinfunction "C_K") (pintype "passive"))
      (node (ref "LED82") (pin "A") (pinfunction "A_A") (pintype "passive"))
      (node (ref "LED93") (pin "K") (pinfunction "C_K") (pintype "passive"))
      (node (ref "LED94") (pin "A") (pinfunction "A_A") (pintype "passive"))
      (node (ref "SV1") (pin "5") (pinfunction "5_5") (pintype "passive"))
    )
    (net (code "8") (name "Net-(LED104-C)") (class "Default")
      (node (ref "LED1") (pin "A") (pinfunction "A_A") (pintype "passive"))
      (node (ref "LED103") (pin "A") (pinfunction "A_A") (pintype "passive"))
      (node (ref "LED104") (pin "K") (pinfunction "C_K") (pintype "passive"))
      (node (ref "LED113") (pin "A") (pinfunction "A_A") (pintype "passive"))
      (node (ref "LED114") (pin "K") (pinfunction "C_K") (pintype "passive"))
      (node (ref "LED121") (pin "A") (pinfunction "A_A") (pintype "passive"))
      (node (ref "LED122") (pin "K") (pinfunction "C_K") (pintype "passive"))
      (node (ref "LED127") (pin "A") (pinfunction "A_A") (pintype "passive"))
      (node (ref "LED128") (pin "K") (pinfunction "C_K") (pintype "passive"))
      (node (ref "LED131") (pin "A") (pinfunction "A_A") (pintype "passive"))
      (node (ref "LED132") (pin "K") (pinfunction "C_K") (pintype "passive"))
      (node (ref "LED2") (pin "K") (pinfunction "C_K") (pintype "passive"))
      (node (ref "LED43") (pin "A") (pinfunction "A_A") (pintype "passive"))
      (node (ref "LED44") (pin "K") (pinfunction "C_K") (pintype "passive"))
      (node (ref "LED61") (pin "A") (pinfunction "A_A") (pintype "passive"))
      (node (ref "LED62") (pin "K") (pinfunction "C_K") (pintype "passive"))
      (node (ref "LED77") (pin "A") (pinfunction "A_A") (pintype "passive"))
      (node (ref "LED78") (pin "K") (pinfunction "C_K") (pintype "passive"))
      (node (ref "LED8") (pin "A") (pinfunction "A_A") (pintype "passive"))
      (node (ref "LED9") (pin "K") (pinfunction "C_K") (pintype "passive"))
      (node (ref "LED91") (pin "A") (pinfunction "A_A") (pintype "passive"))
      (node (ref "LED92") (pin "K") (pinfunction "C_K") (pintype "passive"))
      (node (ref "SV1") (pin "12") (pinfunction "12_12") (pintype "passive"))
    )
    (net (code "9") (name "Net-(LED105-C)") (class "Default")
      (node (ref "LED105") (pin "K") (pinfunction "C_K") (pintype "passive"))
      (node (ref "LED106") (pin "A") (pinfunction "A_A") (pintype "passive"))
      (node (ref "LED113") (pin "K") (pinfunction "C_K") (pintype "passive"))
      (node (ref "LED114") (pin "A") (pinfunction "A_A") (pintype "passive"))
      (node (ref "LED14") (pin "K") (pinfunction "C_K") (pintype "passive"))
      (node (ref "LED15") (pin "A") (pinfunction "A_A") (pintype "passive"))
      (node (ref "LED22") (pin "A") (pinfunction "A_A") (pintype "passive"))
      (node (ref "LED24") (pin "K") (pinfunction "C_K") (pintype "passive"))
      (node (ref "LED35") (pin "K") (pinfunction "C_K") (pintype "passive"))
      (node (ref "LED36") (pin "A") (pinfunction "A_A") (pintype "passive"))
      (node (ref "LED39") (pin "A") (pinfunction "A_A") (pintype "passive"))
      (node (ref "LED40") (pin "K") (pinfunction "C_K") (pintype "passive"))
      (node (ref "LED53") (pin "K") (pinfunction "C_K") (pintype "passive"))
      (node (ref "LED54") (pin "A") (pinfunction "A_A") (pintype "passive"))
      (node (ref "LED59") (pin "A") (pinfunction "A_A") (pintype "passive"))
      (node (ref "LED60") (pin "K") (pinfunction "C_K") (pintype "passive"))
      (node (ref "LED69") (pin "K") (pinfunction "C_K") (pintype "passive"))
      (node (ref "LED70") (pin "A") (pinfunction "A_A") (pintype "passive"))
      (node (ref "LED83") (pin "K") (pinfunction "C_K") (pintype "passive"))
      (node (ref "LED84") (pin "A") (pinfunction "A_A") (pintype "passive"))
      (node (ref "LED95") (pin "K") (pinfunction "C_K") (pintype "passive"))
      (node (ref "LED96") (pin "A") (pinfunction "A_A") (pintype "passive"))
      (node (ref "SV1") (pin "4") (pinfunction "4_4") (pintype "passive"))
    )
    (net (code "10") (name "Net-(LED107-C)") (class "Default")
      (node (ref "LED107") (pin "K") (pinfunction "C_K") (pintype "passive"))
      (node (ref "LED108") (pin "A") (pinfunction "A_A") (pintype "passive"))
      (node (ref "LED115") (pin "K") (pinfunction "C_K") (pintype "passive"))
      (node (ref "LED116") (pin "A") (pinfunction "A_A") (pintype "passive"))
      (node (ref "LED121") (pin "K") (pinfunction "C_K") (pintype "passive"))
      (node (ref "LED122") (pin "A") (pinfunction "A_A") (pintype "passive"))
      (node (ref "LED15") (pin "K") (pinfunction "C_K") (pintype "passive"))
      (node (ref "LED16") (pin "A") (pinfunction "A_A") (pintype "passive"))
      (node (ref "LED24") (pin "A") (pinfunction "A_A") (pintype "passive"))
      (node (ref "LED26") (pin "K") (pinfunction "C_K") (pintype "passive"))
      (node (ref "LED37") (pin "K") (pinfunction "C_K") (pintype "passive"))
      (node (ref "LED38") (pin "A") (pinfunction "A_A") (pintype "passive"))
      (node (ref "LED41") (pin "A") (pinfunction "A_A") (pintype "passive"))
      (node (ref "LED42") (pin "K") (pinfunction "C_K") (pintype "passive"))
      (node (ref "LED55") (pin "K") (pinfunction "C_K") (pintype "passive"))
      (node (ref "LED56") (pin "A") (pinfunction "A_A") (pintype "passive"))
      (node (ref "LED71") (pin "K") (pinfunction "C_K") (pintype "passive"))
      (node (ref "LED72") (pin "A") (pinfunction "A_A") (pintype "passive"))
      (node (ref "LED85") (pin "K") (pinfunction "C_K") (pintype "passive"))
      (node (ref "LED86") (pin "A") (pinfunction "A_A") (pintype "passive"))
      (node (ref "LED97") (pin "K") (pinfunction "C_K") (pintype "passive"))
      (node (ref "LED98") (pin "A") (pinfunction "A_A") (pintype "passive"))
      (node (ref "SV1") (pin "3") (pinfunction "3_3") (pintype "passive"))
    )
    (net (code "11") (name "Net-(LED109-C)") (class "Default")
      (node (ref "LED100") (pin "A") (pinfunction "A_A") (pintype "passive"))
      (node (ref "LED109") (pin "K") (pinfunction "C_K") (pintype "passive"))
      (node (ref "LED110") (pin "A") (pinfunction "A_A") (pintype "passive"))
      (node (ref "LED117") (pin "K") (pinfunction "C_K") (pintype "passive"))
      (node (ref "LED118") (pin "A") (pinfunction "A_A") (pintype "passive"))
      (node (ref "LED123") (pin "K") (pinfunction "C_K") (pintype "passive"))
      (node (ref "LED124") (pin "A") (pinfunction "A_A") (pintype "passive"))
      (node (ref "LED127") (pin "K") (pinfunction "C_K") (pintype "passive"))
      (node (ref "LED128") (pin "A") (pinfunction "A_A") (pintype "passive"))
      (node (ref "LED16") (pin "K") (pinfunction "C_K") (pintype "passive"))
      (node (ref "LED17") (pin "A") (pinfunction "A_A") (pintype "passive"))
      (node (ref "LED25") (pin "K") (pinfunction "C_K") (pintype "passive"))
      (node (ref "LED26") (pin "A") (pinfunction "A_A") (pintype "passive"))
      (node (ref "LED39") (pin "K") (pinfunction "C_K") (pintype "passive"))
      (node (ref "LED40") (pin "A") (pinfunction "A_A") (pintype "passive"))
      (node (ref "LED57") (pin "K") (pinfunction "C_K") (pintype "passive"))
      (node (ref "LED58") (pin "A") (pinfunction "A_A") (pintype "passive"))
      (node (ref "LED73") (pin "K") (pinfunction "C_K") (pintype "passive"))
      (node (ref "LED74") (pin "A") (pinfunction "A_A") (pintype "passive"))
      (node (ref "LED87") (pin "K") (pinfunction "C_K") (pintype "passive"))
      (node (ref "LED88") (pin "A") (pinfunction "A_A") (pintype "passive"))
      (node (ref "LED99") (pin "K") (pinfunction "C_K") (pintype "passive"))
      (node (ref "SV1") (pin "2") (pinfunction "2_2") (pintype "passive"))
    )
    (net (code "12") (name "Net-(LED110-C)") (class "Default")
      (node (ref "LED10") (pin "A") (pinfunction "A_A") (pintype "passive"))
      (node (ref "LED109") (pin "A") (pinfunction "A_A") (pintype "passive"))
      (node (ref "LED110") (pin "K") (pinfunction "C_K") (pintype "passive"))
      (node (ref "LED119") (pin "A") (pinfunction "A_A") (pintype "passive"))
      (node (ref "LED120") (pin "K") (pinfunction "C_K") (pintype "passive"))
      (node (ref "LED13") (pin "K") (pinfunction "C_K") (pintype "passive"))
      (node (ref "LED18") (pin "K") (pinfunction "C_K") (pintype "passive"))
      (node (ref "LED19") (pin "A") (pinfunction "A_A") (pintype "passive"))
      (node (ref "LED29") (pin "A") (pinfunction "A_A") (pintype "passive"))
      (node (ref "LED3") (pin "A") (pinfunction "A_A") (pintype "passive"))
      (node (ref "LED30") (pin "K") (pinfunction "C_K") (pintype "passive"))
      (node (ref "LED43") (pin "K") (pinfunction "C_K") (pintype "passive"))
      (node (ref "LED44") (pin "A") (pinfunction "A_A") (pintype "passive"))
      (node (ref "LED49") (pin "A") (pinfunction "A_A") (pintype "passive"))
      (node (ref "LED50") (pin "K") (pinfunction "C_K") (pintype "passive"))
      (node (ref "LED67") (pin "A") (pinfunction "A_A") (pintype "passive"))
      (node (ref "LED68") (pin "K") (pinfunction "C_K") (pintype "passive"))
      (node (ref "LED7") (pin "K") (pinfunction "C_K") (pintype "passive"))
      (node (ref "LED83") (pin "A") (pinfunction "A_A") (pintype "passive"))
      (node (ref "LED84") (pin "K") (pinfunction "C_K") (pintype "passive"))
      (node (ref "LED97") (pin "A") (pinfunction "A_A") (pintype "passive"))
      (node (ref "LED98") (pin "K") (pinfunction "C_K") (pintype "passive"))
      (node (ref "SV1") (pin "9") (pinfunction "9_9") (pintype "passive"))
    )
    (net (code "13") (name "Net-(LED133-C)") (class "Default")
      (node (ref "LED133") (pin "K") (pinfunction "C_K") (pintype "passive"))
      (node (ref "LED134") (pin "A") (pinfunction "A_A") (pintype "passive"))
      (node (ref "LED135") (pin "A") (pinfunction "A_A") (pintype "passive"))
      (node (ref "LED136") (pin "K") (pinfunction "C_K") (pintype "passive"))
      (node (ref "LED141") (pin "A") (pinfunction "A_A") (pintype "passive"))
      (node (ref "LED142") (pin "K") (pinfunction "C_K") (pintype "passive"))
      (node (ref "SV2") (pin "3") (pinfunction "3_3") (pintype "passive"))
    )
    (net (code "14") (name "Net-(LED134-C)") (class "Default")
      (node (ref "LED133") (pin "A") (pinfunction "A_A") (pintype "passive"))
      (node (ref "LED134") (pin "K") (pinfunction "C_K") (pintype "passive"))
      (node (ref "LED139") (pin "A") (pinfunction "A_A") (pintype "passive"))
      (node (ref "LED140") (pin "K") (pinfunction "C_K") (pintype "passive"))
      (node (ref "LED143") (pin "A") (pinfunction "A_A") (pintype "passive"))
      (node (ref "LED144") (pin "K") (pinfunction "C_K") (pintype "passive"))
      (node (ref "SV2") (pin "4") (pinfunction "4_4") (pintype "passive"))
    )
    (net (code "15") (name "Net-(LED135-C)") (class "Default")
      (node (ref "LED135") (pin "K") (pinfunction "C_K") (pintype "passive"))
      (node (ref "LED136") (pin "A") (pinfunction "A_A") (pintype "passive"))
      (node (ref "LED137") (pin "A") (pinfunction "A_A") (pintype "passive"))
      (node (ref "LED138") (pin "K") (pinfunction "C_K") (pintype "passive"))
      (node (ref "LED139") (pin "K") (pinfunction "C_K") (pintype "passive"))
      (node (ref "LED140") (pin "A") (pinfunction "A_A") (pintype "passive"))
      (node (ref "SV2") (pin "2") (pinfunction "2_2") (pintype "passive"))
    )
    (net (code "16") (name "Net-(LED137-C)") (class "Default")
      (node (ref "LED137") (pin "K") (pinfunction "C_K") (pintype "passive"))
      (node (ref "LED138") (pin "A") (pinfunction "A_A") (pintype "passive"))
      (node (ref "LED141") (pin "K") (pinfunction "C_K") (pintype "passive"))
      (node (ref "LED142") (pin "A") (pinfunction "A_A") (pintype "passive"))
      (node (ref "LED143") (pin "K") (pinfunction "C_K") (pintype "passive"))
      (node (ref "LED144") (pin "A") (pinfunction "A_A") (pintype "passive"))
      (node (ref "SV2") (pin "1") (pinfunction "1_1") (pintype "passive"))
    )
  )
)
